# FPGA_SYSTERM.net
KiCad netlist of a schematic drawn in Altium Designer
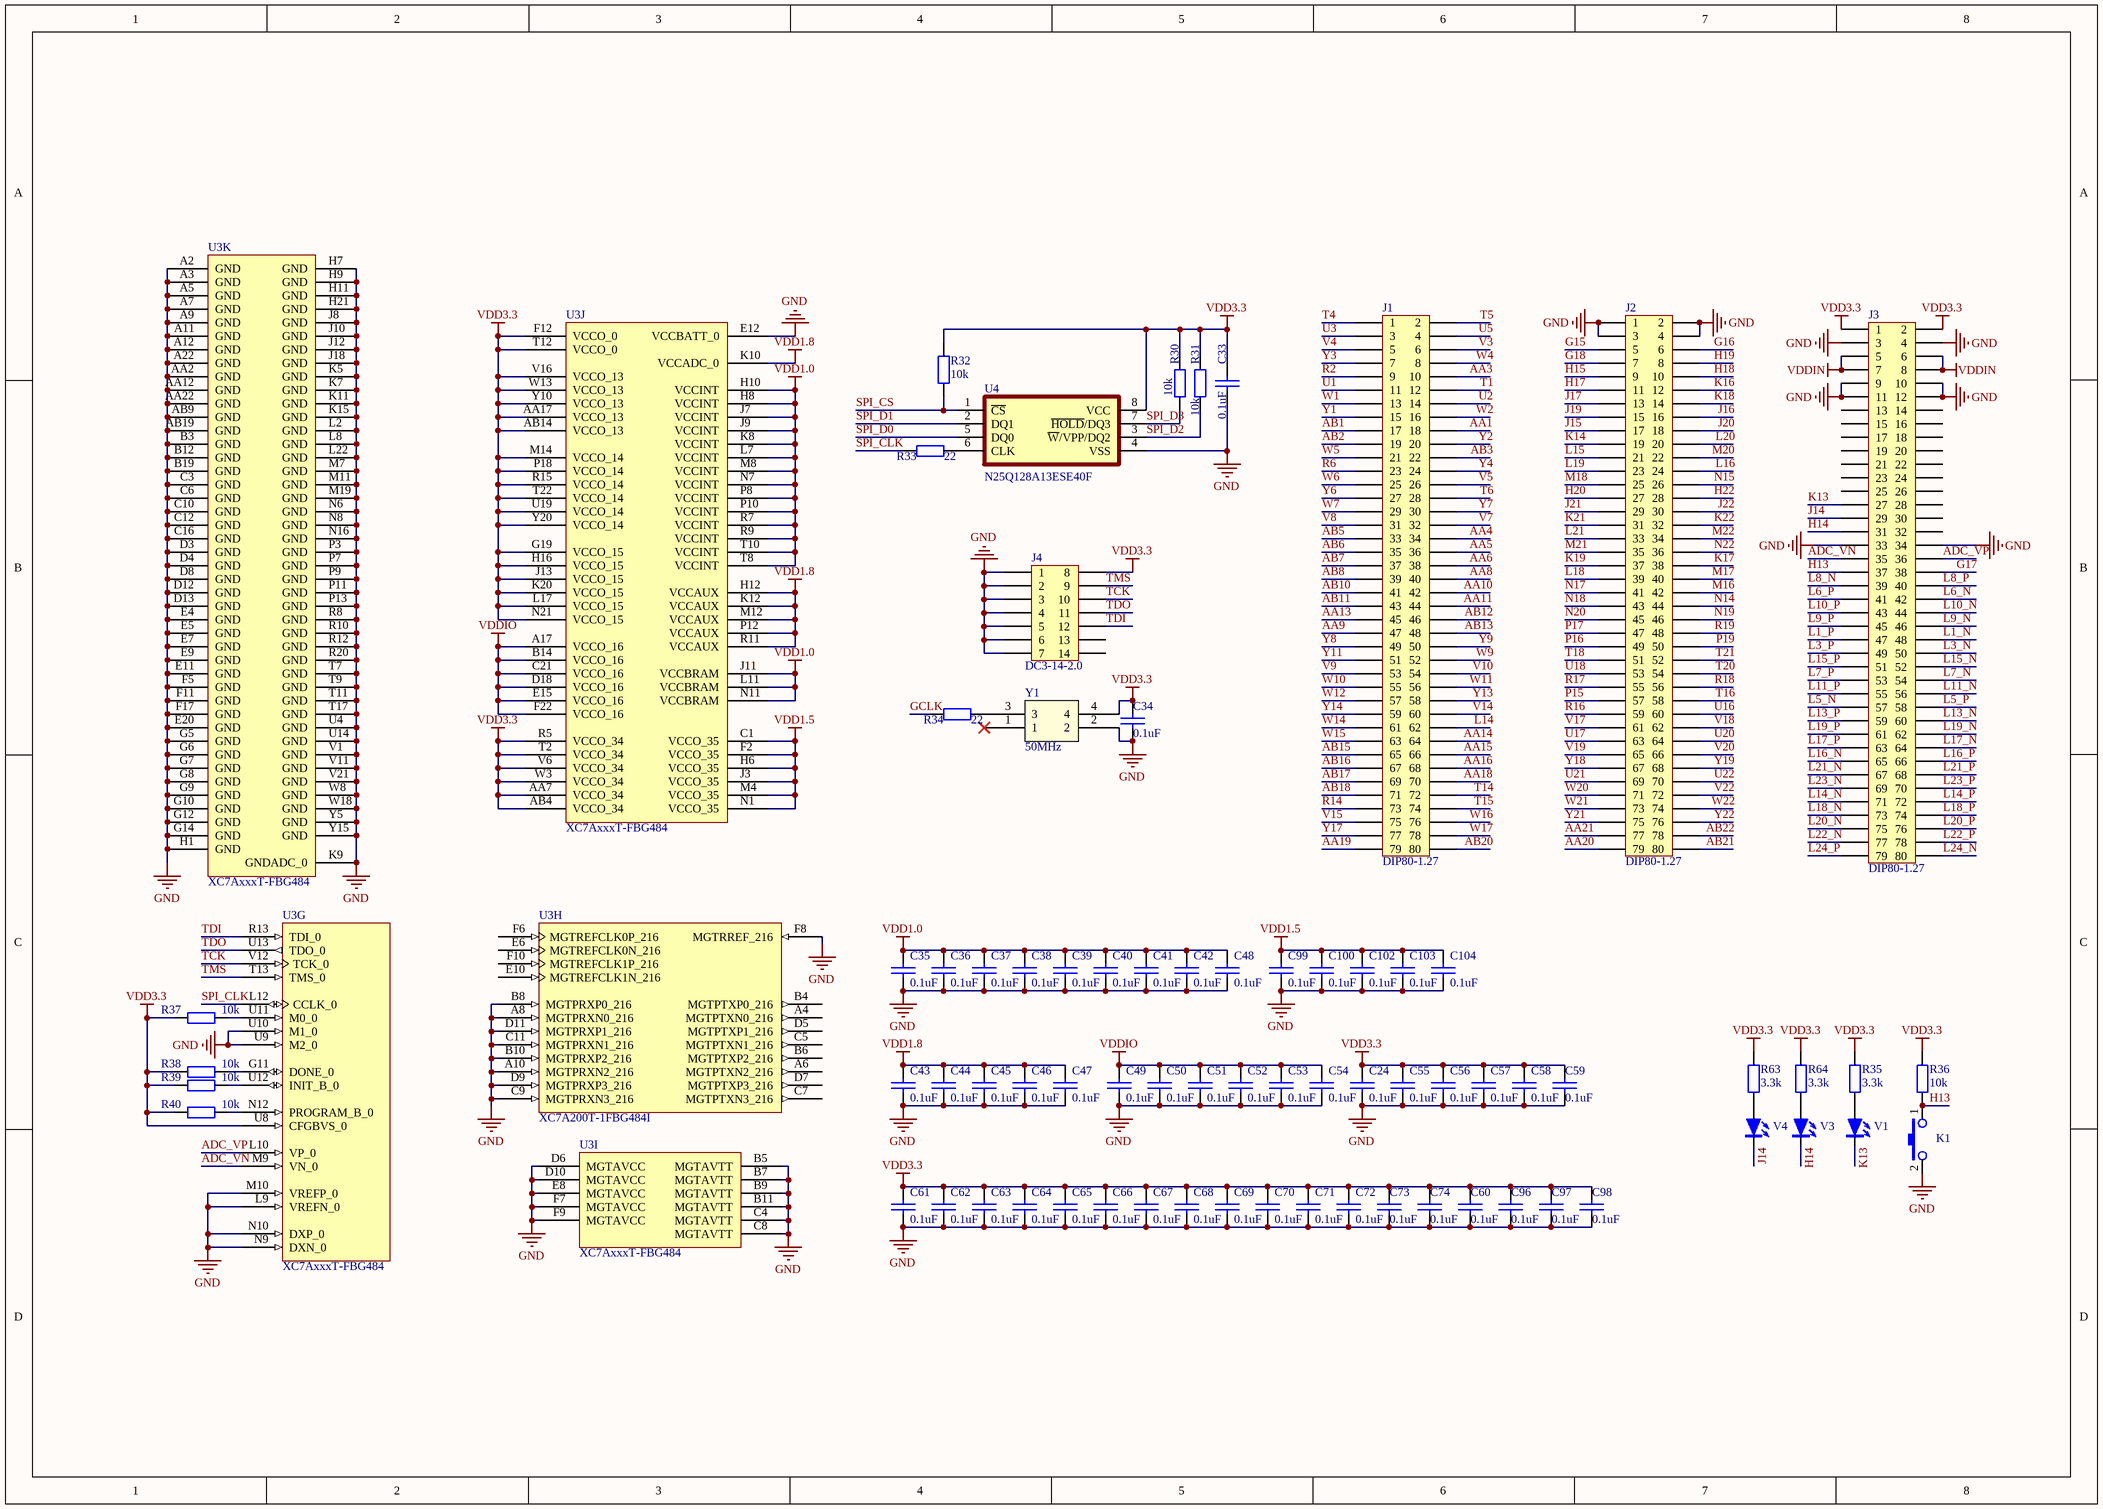
[diagram p0: FPGA SYSTERM.SchDoc]

(export (version "E")
  (design (tool "Eeschema 10.0.6"))
  (components
    (comp (ref "C24") (value "0.1uF") (footprint "0402_c_m") (libsource (lib "My library") (part "CAP")))
    (comp (ref "C33") (value "0.1uF") (footprint "0402_C_M") (libsource (lib "Component") (part "CAP")))
    (comp (ref "C34") (value "0.1uF") (footprint "0402_C_M") (libsource (lib "Component") (part "CAP")))
    (comp (ref "C35") (value "0.1uF") (footprint "0402_C_M") (libsource (lib "Component") (part "CAP")))
    (comp (ref "C36") (value "0.1uF") (footprint "0402_C_M") (libsource (lib "Component") (part "CAP")))
    (comp (ref "C37") (value "0.1uF") (footprint "0402_C_M") (libsource (lib "Component") (part "CAP")))
    (comp (ref "C38") (value "0.1uF") (footprint "0402_C_M") (libsource (lib "Component") (part "CAP")))
    (comp (ref "C39") (value "0.1uF") (footprint "0402_C_M") (libsource (lib "Component") (part "CAP")))
    (comp (ref "C40") (value "0.1uF") (footprint "0402_C_M") (libsource (lib "Component") (part "CAP")))
    (comp (ref "C41") (value "0.1uF") (footprint "0402_C_M") (libsource (lib "Component") (part "CAP")))
    (comp (ref "C42") (value "0.1uF") (footprint "0402_C_M") (libsource (lib "Component") (part "CAP")))
    (comp (ref "C43") (value "0.1uF") (footprint "0402_C_M") (libsource (lib "Component") (part "CAP")))
    (comp (ref "C44") (value "0.1uF") (footprint "0402_C_M") (libsource (lib "Component") (part "CAP")))
    (comp (ref "C45") (value "0.1uF") (footprint "0402_C_M") (libsource (lib "Component") (part "CAP")))
    (comp (ref "C46") (value "0.1uF") (footprint "0402_C_M") (libsource (lib "Component") (part "CAP")))
    (comp (ref "C47") (value "0.1uF") (footprint "0402_C_M") (libsource (lib "Component") (part "CAP")))
    (comp (ref "C48") (value "0.1uF") (footprint "0402_C_M") (libsource (lib "Component") (part "CAP")))
    (comp (ref "C49") (value "0.1uF") (footprint "0402_C_M") (libsource (lib "Component") (part "CAP")))
    (comp (ref "C50") (value "0.1uF") (footprint "0402_C_M") (libsource (lib "Component") (part "CAP")))
    (comp (ref "C51") (value "0.1uF") (footprint "0402_C_M") (libsource (lib "Component") (part "CAP")))
    (comp (ref "C52") (value "0.1uF") (footprint "0402_C_M") (libsource (lib "Component") (part "CAP")))
    (comp (ref "C53") (value "0.1uF") (footprint "0402_C_M") (libsource (lib "Component") (part "CAP")))
    (comp (ref "C54") (value "0.1uF") (footprint "0402_C_M") (libsource (lib "Component") (part "CAP")))
    (comp (ref "C55") (value "0.1uF") (footprint "0402_C_M") (libsource (lib "Component") (part "CAP")))
    (comp (ref "C56") (value "0.1uF") (footprint "0402_C_M") (libsource (lib "Component") (part "CAP")))
    (comp (ref "C57") (value "0.1uF") (footprint "0402_C_M") (libsource (lib "Component") (part "CAP")))
    (comp (ref "C58") (value "0.1uF") (footprint "0402_C_M") (libsource (lib "Component") (part "CAP")))
    (comp (ref "C59") (value "0.1uF") (footprint "0402_C_M") (libsource (lib "Component") (part "CAP")))
    (comp (ref "C60") (value "0.1uF") (footprint "0402_C_M") (libsource (lib "Component") (part "CAP")))
    (comp (ref "C61") (value "0.1uF") (footprint "0402_C_M") (libsource (lib "Component") (part "CAP")))
    (comp (ref "C62") (value "0.1uF") (footprint "0402_C_M") (libsource (lib "Component") (part "CAP")))
    (comp (ref "C63") (value "0.1uF") (footprint "0402_C_M") (libsource (lib "Component") (part "CAP")))
    (comp (ref "C64") (value "0.1uF") (footprint "0402_C_M") (libsource (lib "Component") (part "CAP")))
    (comp (ref "C65") (value "0.1uF") (footprint "0402_C_M") (libsource (lib "Component") (part "CAP")))
    (comp (ref "C66") (value "0.1uF") (footprint "0402_C_M") (libsource (lib "Component") (part "CAP")))
    (comp (ref "C67") (value "0.1uF") (footprint "0402_C_M") (libsource (lib "Component") (part "CAP")))
    (comp (ref "C68") (value "0.1uF") (footprint "0402_C_M") (libsource (lib "Component") (part "CAP")))
    (comp (ref "C69") (value "0.1uF") (footprint "0402_C_M") (libsource (lib "Component") (part "CAP")))
    (comp (ref "C70") (value "0.1uF") (footprint "0402_C_M") (libsource (lib "Component") (part "CAP")))
    (comp (ref "C71") (value "0.1uF") (footprint "0402_C_M") (libsource (lib "Component") (part "CAP")))
    (comp (ref "C72") (value "0.1uF") (footprint "0402_C_M") (libsource (lib "Component") (part "CAP")))
    (comp (ref "C73") (value "0.1uF") (footprint "0402_C_M") (libsource (lib "Component") (part "CAP")))
    (comp (ref "C74") (value "0.1uF") (footprint "0402_C_M") (libsource (lib "Component") (part "CAP")))
    (comp (ref "C96") (value "0.1uF") (footprint "0402_C_M") (libsource (lib "Component") (part "CAP")))
    (comp (ref "C97") (value "0.1uF") (footprint "0402_C_M") (libsource (lib "Component") (part "CAP")))
    (comp (ref "C98") (value "0.1uF") (footprint "0402_C_M") (libsource (lib "Component") (part "CAP")))
    (comp (ref "C99") (value "0.1uF") (footprint "0402_C_M") (libsource (lib "Component") (part "CAP")))
    (comp (ref "C100") (value "0.1uF") (footprint "0402_C_M") (libsource (lib "Component") (part "CAP")))
    (comp (ref "C102") (value "0.1uF") (footprint "0402_C_M") (libsource (lib "Component") (part "CAP")))
    (comp (ref "C103") (value "0.1uF") (footprint "0402_C_M") (libsource (lib "Component") (part "CAP")))
    (comp (ref "C104") (value "0.1uF") (footprint "0402_C_M") (libsource (lib "Component") (part "CAP")))
    (comp (ref "J1")
      (value "DIP80-1.27")
      (footprint "DIP1.27-80")
      (libsource (lib "DIP_SIP") (part "CON80_1"))
    )
    (comp (ref "J2")
      (value "DIP80-1.27")
      (footprint "DIP1.27-80")
      (libsource (lib "DIP_SIP") (part "CON80_1"))
    )
    (comp (ref "J3")
      (value "DIP80-1.27")
      (footprint "DIP1.27-80")
      (libsource (lib "DIP_SIP") (part "CON80_1"))
    )
    (comp (ref "J4") (value "DC3-14-2.0") (footprint "DC3-14-2.0") (libsource (lib "DIP_SIP") (part "CON14")))
    (comp (ref "K1") (value "KEY") (footprint "KEY2") (libsource (lib "Common") (part "KEY1")))
    (comp (ref "R30") (value "10k") (footprint "0402_R_M") (libsource (lib "Common") (part "RES2")))
    (comp (ref "R31") (value "10k") (footprint "0402_R_M") (libsource (lib "Common") (part "RES2")))
    (comp (ref "R32") (value "10k") (footprint "0402_R_M") (libsource (lib "often") (part "RES2")))
    (comp (ref "R33") (value "22") (footprint "0402_R_M") (libsource (lib "Common") (part "RES2")))
    (comp (ref "R34") (value "22") (footprint "0402_R_M") (libsource (lib "Common") (part "RES2")))
    (comp (ref "R35") (value "3.3k") (footprint "0402_R_M") (libsource (lib "Common") (part "RES2")))
    (comp (ref "R36") (value "10k") (footprint "0402_R_M") (libsource (lib "Common") (part "RES2")))
    (comp (ref "R37") (value "10k") (footprint "0402_R_M") (libsource (lib "Common") (part "RES2")))
    (comp (ref "R38") (value "10k") (footprint "0402_R_M") (libsource (lib "Common") (part "RES2")))
    (comp (ref "R39") (value "10k") (footprint "0402_R_M") (libsource (lib "Common") (part "RES2")))
    (comp (ref "R40") (value "10k") (footprint "0402_R_M") (libsource (lib "Common") (part "RES2")))
    (comp (ref "R63") (value "3.3k") (footprint "0402_R_M") (libsource (lib "Common") (part "RES2")))
    (comp (ref "R64") (value "3.3k") (footprint "0402_R_M") (libsource (lib "Common") (part "RES2")))
    (comp (ref "U3")
      (value "XC7AxxxT-FBG484")
      (footprint "FBG484")
      (description "Artix-7 FPGA, 285 User I/Os, 4 GTP, 484-Ball BGA, Speed Grade 1, Industrial Grade, Pb-Free")
      (fields (field (name "GENERIC PART NUMBER") "XC7A200T") (field (name "MANUFACTURER") "Xilinx"))
      (libsource (lib "My Library") (part "XC7A200T-1FBG484I"))
    )
    (comp (ref "U4")
      (value "N25Q128A13ESE40F")
      (footprint "SOP8W")
      (libsource (lib "IC") (part "N25Q128A11EF840E"))
    )
    (comp (ref "V1") (value "LED") (footprint "0805D") (libsource (lib "发光管、数码管") (part "LED2")))
    (comp (ref "V3") (value "LED") (footprint "0805D") (libsource (lib "发光管、数码管") (part "LED2")))
    (comp (ref "V4") (value "LED") (footprint "0805D") (libsource (lib "发光管、数码管") (part "LED2")))
    (comp (ref "Y1")
      (value "50MHz")
      (footprint "OSC 7050-4P")
      (libsource (lib "micro.logic-v1.0") (part "XTAL"))
    )
  )
  (nets
    (net (code "1") (name "/AA1") (class "Default")
      (node (ref "J1") (pin "18") (pinfunction "18_18") (pintype "passive"))
    )
    (net (code "2") (name "/AA3") (class "Default")
      (node (ref "J1") (pin "10") (pinfunction "10_10") (pintype "passive"))
    )
    (net (code "3") (name "/AA4") (class "Default")
      (node (ref "J1") (pin "34") (pinfunction "34_34") (pintype "passive"))
    )
    (net (code "4") (name "/AA5") (class "Default")
      (node (ref "J1") (pin "36") (pinfunction "36_36") (pintype "passive"))
    )
    (net (code "5") (name "/AA6") (class "Default")
      (node (ref "J1") (pin "38") (pinfunction "38_38") (pintype "passive"))
    )
    (net (code "6") (name "/AA8") (class "Default")
      (node (ref "J1") (pin "40") (pinfunction "40_40") (pintype "passive"))
    )
    (net (code "7") (name "/AA9") (class "Default")
      (node (ref "J1") (pin "47") (pinfunction "47_47") (pintype "passive"))
    )
    (net (code "8") (name "/AA10") (class "Default")
      (node (ref "J1") (pin "42") (pinfunction "42_42") (pintype "passive"))
    )
    (net (code "9") (name "/AA11") (class "Default")
      (node (ref "J1") (pin "44") (pinfunction "44_44") (pintype "passive"))
    )
    (net (code "10") (name "/AA13") (class "Default")
      (node (ref "J1") (pin "45") (pinfunction "45_45") (pintype "passive"))
    )
    (net (code "11") (name "/AA14") (class "Default")
      (node (ref "J1") (pin "64") (pinfunction "64_64") (pintype "passive"))
    )
    (net (code "12") (name "/AA15") (class "Default")
      (node (ref "J1") (pin "66") (pinfunction "66_66") (pintype "passive"))
    )
    (net (code "13") (name "/AA16") (class "Default")
      (node (ref "J1") (pin "68") (pinfunction "68_68") (pintype "passive"))
    )
    (net (code "14") (name "/AA18") (class "Default")
      (node (ref "J1") (pin "70") (pinfunction "70_70") (pintype "passive"))
    )
    (net (code "15") (name "/AA19") (class "Default")
      (node (ref "J1") (pin "79") (pinfunction "79_79") (pintype "passive"))
    )
    (net (code "16") (name "/AA20") (class "Default")
      (node (ref "J2") (pin "79") (pinfunction "79_79") (pintype "passive"))
    )
    (net (code "17") (name "/AA21") (class "Default")
      (node (ref "J2") (pin "77") (pinfunction "77_77") (pintype "passive"))
    )
    (net (code "18") (name "/AB1") (class "Default")
      (node (ref "J1") (pin "17") (pinfunction "17_17") (pintype "passive"))
    )
    (net (code "19") (name "/AB2") (class "Default")
      (node (ref "J1") (pin "19") (pinfunction "19_19") (pintype "passive"))
    )
    (net (code "20") (name "/AB3") (class "Default")
      (node (ref "J1") (pin "22") (pinfunction "22_22") (pintype "passive"))
    )
    (net (code "21") (name "/AB5") (class "Default")
      (node (ref "J1") (pin "33") (pinfunction "33_33") (pintype "passive"))
    )
    (net (code "22") (name "/AB6") (class "Default")
      (node (ref "J1") (pin "35") (pinfunction "35_35") (pintype "passive"))
    )
    (net (code "23") (name "/AB7") (class "Default")
      (node (ref "J1") (pin "37") (pinfunction "37_37") (pintype "passive"))
    )
    (net (code "24") (name "/AB8") (class "Default")
      (node (ref "J1") (pin "39") (pinfunction "39_39") (pintype "passive"))
    )
    (net (code "25") (name "/AB10") (class "Default")
      (node (ref "J1") (pin "41") (pinfunction "41_41") (pintype "passive"))
    )
    (net (code "26") (name "/AB11") (class "Default")
      (node (ref "J1") (pin "43") (pinfunction "43_43") (pintype "passive"))
    )
    (net (code "27") (name "/AB12") (class "Default")
      (node (ref "J1") (pin "46") (pinfunction "46_46") (pintype "passive"))
    )
    (net (code "28") (name "/AB13") (class "Default")
      (node (ref "J1") (pin "48") (pinfunction "48_48") (pintype "passive"))
    )
    (net (code "29") (name "/AB15") (class "Default")
      (node (ref "J1") (pin "65") (pinfunction "65_65") (pintype "passive"))
    )
    (net (code "30") (name "/AB16") (class "Default")
      (node (ref "J1") (pin "67") (pinfunction "67_67") (pintype "passive"))
    )
    (net (code "31") (name "/AB17") (class "Default")
      (node (ref "J1") (pin "69") (pinfunction "69_69") (pintype "passive"))
    )
    (net (code "32") (name "/AB18") (class "Default")
      (node (ref "J1") (pin "71") (pinfunction "71_71") (pintype "passive"))
    )
    (net (code "33") (name "/AB20") (class "Default")
      (node (ref "J1") (pin "80") (pinfunction "80_80") (pintype "passive"))
    )
    (net (code "34") (name "/AB21") (class "Default")
      (node (ref "J2") (pin "80") (pinfunction "80_80") (pintype "passive"))
    )
    (net (code "35") (name "/AB22") (class "Default")
      (node (ref "J2") (pin "78") (pinfunction "78_78") (pintype "passive"))
    )
    (net (code "36") (name "/ADC_VN") (class "Default")
      (node (ref "J3") (pin "35") (pinfunction "35_35") (pintype "passive"))
      (node (ref "U3") (pin "M9") (pinfunction "VN_0_M9") (pintype "input"))
    )
    (net (code "37") (name "/ADC_VP") (class "Default")
      (node (ref "J3") (pin "36") (pinfunction "36_36") (pintype "passive"))
      (node (ref "U3") (pin "L10") (pinfunction "VP_0_L10") (pintype "input"))
    )
    (net (code "38") (name "/G15") (class "Default")
      (node (ref "J2") (pin "5") (pinfunction "5_5") (pintype "passive"))
    )
    (net (code "39") (name "/G16") (class "Default")
      (node (ref "J2") (pin "6") (pinfunction "6_6") (pintype "passive"))
    )
    (net (code "40") (name "/G17") (class "Default")
      (node (ref "J3") (pin "38") (pinfunction "38_38") (pintype "passive"))
    )
    (net (code "41") (name "/G18") (class "Default")
      (node (ref "J2") (pin "7") (pinfunction "7_7") (pintype "passive"))
    )
    (net (code "42") (name "/GCLK") (class "Default") (node (ref "R34") (pin "2") (pintype "passive")))
    (net (code "43") (name "/H13") (class "Default")
      (node (ref "J3") (pin "37") (pinfunction "37_37") (pintype "passive"))
      (node (ref "K1") (pin "1") (pintype "passive"))
      (node (ref "R36") (pin "1") (pintype "passive"))
    )
    (net (code "44") (name "/H14") (class "Default")
      (node (ref "J3") (pin "31") (pinfunction "31_31") (pintype "passive"))
      (node (ref "V3") (pin "2") (pinfunction "2_2") (pintype "passive"))
    )
    (net (code "45") (name "/H15") (class "Default")
      (node (ref "J2") (pin "9") (pinfunction "9_9") (pintype "passive"))
    )
    (net (code "46") (name "/H17") (class "Default")
      (node (ref "J2") (pin "11") (pinfunction "11_11") (pintype "passive"))
    )
    (net (code "47") (name "/H18") (class "Default")
      (node (ref "J2") (pin "10") (pinfunction "10_10") (pintype "passive"))
    )
    (net (code "48") (name "/H19") (class "Default")
      (node (ref "J2") (pin "8") (pinfunction "8_8") (pintype "passive"))
    )
    (net (code "49") (name "/H20") (class "Default")
      (node (ref "J2") (pin "27") (pinfunction "27_27") (pintype "passive"))
    )
    (net (code "50") (name "/H22") (class "Default")
      (node (ref "J2") (pin "28") (pinfunction "28_28") (pintype "passive"))
    )
    (net (code "51") (name "/J14") (class "Default")
      (node (ref "J3") (pin "29") (pinfunction "29_29") (pintype "passive"))
      (node (ref "V4") (pin "2") (pinfunction "2_2") (pintype "passive"))
    )
    (net (code "52") (name "/J15") (class "Default")
      (node (ref "J2") (pin "17") (pinfunction "17_17") (pintype "passive"))
    )
    (net (code "53") (name "/J16") (class "Default")
      (node (ref "J2") (pin "16") (pinfunction "16_16") (pintype "passive"))
    )
    (net (code "54") (name "/J17") (class "Default")
      (node (ref "J2") (pin "13") (pinfunction "13_13") (pintype "passive"))
    )
    (net (code "55") (name "/J19") (class "Default")
      (node (ref "J2") (pin "15") (pinfunction "15_15") (pintype "passive"))
    )
    (net (code "56") (name "/J20") (class "Default")
      (node (ref "J2") (pin "18") (pinfunction "18_18") (pintype "passive"))
    )
    (net (code "57") (name "/J21") (class "Default")
      (node (ref "J2") (pin "29") (pinfunction "29_29") (pintype "passive"))
    )
    (net (code "58") (name "/J22") (class "Default")
      (node (ref "J2") (pin "30") (pinfunction "30_30") (pintype "passive"))
    )
    (net (code "59") (name "/K13") (class "Default")
      (node (ref "J3") (pin "27") (pinfunction "27_27") (pintype "passive"))
      (node (ref "V1") (pin "2") (pinfunction "2_2") (pintype "passive"))
    )
    (net (code "60") (name "/K14") (class "Default")
      (node (ref "J2") (pin "19") (pinfunction "19_19") (pintype "passive"))
    )
    (net (code "61") (name "/K16") (class "Default")
      (node (ref "J2") (pin "12") (pinfunction "12_12") (pintype "passive"))
    )
    (net (code "62") (name "/K17") (class "Default")
      (node (ref "J2") (pin "38") (pinfunction "38_38") (pintype "passive"))
    )
    (net (code "63") (name "/K18") (class "Default")
      (node (ref "J2") (pin "14") (pinfunction "14_14") (pintype "passive"))
    )
    (net (code "64") (name "/K19") (class "Default")
      (node (ref "J2") (pin "37") (pinfunction "37_37") (pintype "passive"))
    )
    (net (code "65") (name "/K21") (class "Default")
      (node (ref "J2") (pin "31") (pinfunction "31_31") (pintype "passive"))
    )
    (net (code "66") (name "/K22") (class "Default")
      (node (ref "J2") (pin "32") (pinfunction "32_32") (pintype "passive"))
    )
    (net (code "67") (name "/L1_N") (class "Default")
      (node (ref "J3") (pin "48") (pinfunction "48_48") (pintype "passive"))
    )
    (net (code "68") (name "/L1_P") (class "Default")
      (node (ref "J3") (pin "47") (pinfunction "47_47") (pintype "passive"))
    )
    (net (code "69") (name "/L3_N") (class "Default")
      (node (ref "J3") (pin "50") (pinfunction "50_50") (pintype "passive"))
    )
    (net (code "70") (name "/L3_P") (class "Default")
      (node (ref "J3") (pin "49") (pinfunction "49_49") (pintype "passive"))
    )
    (net (code "71") (name "/L5_N") (class "Default")
      (node (ref "J3") (pin "57") (pinfunction "57_57") (pintype "passive"))
    )
    (net (code "72") (name "/L5_P") (class "Default")
      (node (ref "J3") (pin "58") (pinfunction "58_58") (pintype "passive"))
    )
    (net (code "73") (name "/L6_N") (class "Default")
      (node (ref "J3") (pin "42") (pinfunction "42_42") (pintype "passive"))
    )
    (net (code "74") (name "/L6_P") (class "Default")
      (node (ref "J3") (pin "41") (pinfunction "41_41") (pintype "passive"))
    )
    (net (code "75") (name "/L7_N") (class "Default")
      (node (ref "J3") (pin "54") (pinfunction "54_54") (pintype "passive"))
    )
    (net (code "76") (name "/L7_P") (class "Default")
      (node (ref "J3") (pin "53") (pinfunction "53_53") (pintype "passive"))
    )
    (net (code "77") (name "/L8_N") (class "Default")
      (node (ref "J3") (pin "39") (pinfunction "39_39") (pintype "passive"))
    )
    (net (code "78") (name "/L8_P") (class "Default")
      (node (ref "J3") (pin "40") (pinfunction "40_40") (pintype "passive"))
    )
    (net (code "79") (name "/L9_N") (class "Default")
      (node (ref "J3") (pin "46") (pinfunction "46_46") (pintype "passive"))
    )
    (net (code "80") (name "/L9_P") (class "Default")
      (node (ref "J3") (pin "45") (pinfunction "45_45") (pintype "passive"))
    )
    (net (code "81") (name "/L10_N") (class "Default")
      (node (ref "J3") (pin "44") (pinfunction "44_44") (pintype "passive"))
    )
    (net (code "82") (name "/L10_P") (class "Default")
      (node (ref "J3") (pin "43") (pinfunction "43_43") (pintype "passive"))
    )
    (net (code "83") (name "/L11_N") (class "Default")
      (node (ref "J3") (pin "56") (pinfunction "56_56") (pintype "passive"))
    )
    (net (code "84") (name "/L11_P") (class "Default")
      (node (ref "J3") (pin "55") (pinfunction "55_55") (pintype "passive"))
    )
    (net (code "85") (name "/L13_N") (class "Default")
      (node (ref "J3") (pin "60") (pinfunction "60_60") (pintype "passive"))
    )
    (net (code "86") (name "/L13_P") (class "Default")
      (node (ref "J3") (pin "59") (pinfunction "59_59") (pintype "passive"))
    )
    (net (code "87") (name "/L14") (class "Default")
      (node (ref "J1") (pin "62") (pinfunction "62_62") (pintype "passive"))
    )
    (net (code "88") (name "/L14_N") (class "Default")
      (node (ref "J3") (pin "71") (pinfunction "71_71") (pintype "passive"))
    )
    (net (code "89") (name "/L14_P") (class "Default")
      (node (ref "J3") (pin "72") (pinfunction "72_72") (pintype "passive"))
    )
    (net (code "90") (name "/L15") (class "Default")
      (node (ref "J2") (pin "21") (pinfunction "21_21") (pintype "passive"))
    )
    (net (code "91") (name "/L15_N") (class "Default")
      (node (ref "J3") (pin "52") (pinfunction "52_52") (pintype "passive"))
    )
    (net (code "92") (name "/L15_P") (class "Default")
      (node (ref "J3") (pin "51") (pinfunction "51_51") (pintype "passive"))
    )
    (net (code "93") (name "/L16") (class "Default")
      (node (ref "J2") (pin "24") (pinfunction "24_24") (pintype "passive"))
    )
    (net (code "94") (name "/L16_N") (class "Default")
      (node (ref "J3") (pin "65") (pinfunction "65_65") (pintype "passive"))
    )
    (net (code "95") (name "/L16_P") (class "Default")
      (node (ref "J3") (pin "66") (pinfunction "66_66") (pintype "passive"))
    )
    (net (code "96") (name "/L17_N") (class "Default")
      (node (ref "J3") (pin "64") (pinfunction "64_64") (pintype "passive"))
    )
    (net (code "97") (name "/L17_P") (class "Default")
      (node (ref "J3") (pin "63") (pinfunction "63_63") (pintype "passive"))
    )
    (net (code "98") (name "/L18") (class "Default")
      (node (ref "J2") (pin "39") (pinfunction "39_39") (pintype "passive"))
    )
    (net (code "99") (name "/L18_N") (class "Default")
      (node (ref "J3") (pin "73") (pinfunction "73_73") (pintype "passive"))
    )
    (net (code "100") (name "/L18_P") (class "Default")
      (node (ref "J3") (pin "74") (pinfunction "74_74") (pintype "passive"))
    )
    (net (code "101") (name "/L19") (class "Default")
      (node (ref "J2") (pin "23") (pinfunction "23_23") (pintype "passive"))
    )
    (net (code "102") (name "/L19_N") (class "Default")
      (node (ref "J3") (pin "62") (pinfunction "62_62") (pintype "passive"))
    )
    (net (code "103") (name "/L19_P") (class "Default")
      (node (ref "J3") (pin "61") (pinfunction "61_61") (pintype "passive"))
    )
    (net (code "104") (name "/L20") (class "Default")
      (node (ref "J2") (pin "20") (pinfunction "20_20") (pintype "passive"))
    )
    (net (code "105") (name "/L20_N") (class "Default")
      (node (ref "J3") (pin "75") (pinfunction "75_75") (pintype "passive"))
    )
    (net (code "106") (name "/L20_P") (class "Default")
      (node (ref "J3") (pin "76") (pinfunction "76_76") (pintype "passive"))
    )
    (net (code "107") (name "/L21") (class "Default")
      (node (ref "J2") (pin "33") (pinfunction "33_33") (pintype "passive"))
    )
    (net (code "108") (name "/L21_N") (class "Default")
      (node (ref "J3") (pin "67") (pinfunction "67_67") (pintype "passive"))
    )
    (net (code "109") (name "/L21_P") (class "Default")
      (node (ref "J3") (pin "68") (pinfunction "68_68") (pintype "passive"))
    )
    (net (code "110") (name "/L22_N") (class "Default")
      (node (ref "J3") (pin "77") (pinfunction "77_77") (pintype "passive"))
    )
    (net (code "111") (name "/L22_P") (class "Default")
      (node (ref "J3") (pin "78") (pinfunction "78_78") (pintype "passive"))
    )
    (net (code "112") (name "/L23_N") (class "Default")
      (node (ref "J3") (pin "69") (pinfunction "69_69") (pintype "passive"))
    )
    (net (code "113") (name "/L23_P") (class "Default")
      (node (ref "J3") (pin "70") (pinfunction "70_70") (pintype "passive"))
    )
    (net (code "114") (name "/L24_N") (class "Default")
      (node (ref "J3") (pin "80") (pinfunction "80_80") (pintype "passive"))
    )
    (net (code "115") (name "/L24_P") (class "Default")
      (node (ref "J3") (pin "79") (pinfunction "79_79") (pintype "passive"))
    )
    (net (code "116") (name "/M16") (class "Default")
      (node (ref "J2") (pin "42") (pinfunction "42_42") (pintype "passive"))
    )
    (net (code "117") (name "/M17") (class "Default")
      (node (ref "J2") (pin "40") (pinfunction "40_40") (pintype "passive"))
    )
    (net (code "118") (name "/M18") (class "Default")
      (node (ref "J2") (pin "25") (pinfunction "25_25") (pintype "passive"))
    )
    (net (code "119") (name "/M20") (class "Default")
      (node (ref "J2") (pin "22") (pinfunction "22_22") (pintype "passive"))
    )
    (net (code "120") (name "/M21") (class "Default")
      (node (ref "J2") (pin "35") (pinfunction "35_35") (pintype "passive"))
    )
    (net (code "121") (name "/M22") (class "Default")
      (node (ref "J2") (pin "34") (pinfunction "34_34") (pintype "passive"))
    )
    (net (code "122") (name "/N14") (class "Default")
      (node (ref "J2") (pin "44") (pinfunction "44_44") (pintype "passive"))
    )
    (net (code "123") (name "/N15") (class "Default")
      (node (ref "J2") (pin "26") (pinfunction "26_26") (pintype "passive"))
    )
    (net (code "124") (name "/N17") (class "Default")
      (node (ref "J2") (pin "41") (pinfunction "41_41") (pintype "passive"))
    )
    (net (code "125") (name "/N18") (class "Default")
      (node (ref "J2") (pin "43") (pinfunction "43_43") (pintype "passive"))
    )
    (net (code "126") (name "/N19") (class "Default")
      (node (ref "J2") (pin "46") (pinfunction "46_46") (pintype "passive"))
    )
    (net (code "127") (name "/N20") (class "Default")
      (node (ref "J2") (pin "45") (pinfunction "45_45") (pintype "passive"))
    )
    (net (code "128") (name "/N22") (class "Default")
      (node (ref "J2") (pin "36") (pinfunction "36_36") (pintype "passive"))
    )
    (net (code "129") (name "/P15") (class "Default")
      (node (ref "J2") (pin "57") (pinfunction "57_57") (pintype "passive"))
    )
    (net (code "130") (name "/P16") (class "Default")
      (node (ref "J2") (pin "49") (pinfunction "49_49") (pintype "passive"))
    )
    (net (code "131") (name "/P17") (class "Default")
      (node (ref "J2") (pin "47") (pinfunction "47_47") (pintype "passive"))
    )
    (net (code "132") (name "/P19") (class "Default")
      (node (ref "J2") (pin "50") (pinfunction "50_50") (pintype "passive"))
    )
    (net (code "133") (name "/R2") (class "Default")
      (node (ref "J1") (pin "9") (pinfunction "9_9") (pintype "passive"))
    )
    (net (code "134") (name "/R6") (class "Default")
      (node (ref "J1") (pin "23") (pinfunction "23_23") (pintype "passive"))
    )
    (net (code "135") (name "/R14") (class "Default")
      (node (ref "J1") (pin "73") (pinfunction "73_73") (pintype "passive"))
    )
    (net (code "136") (name "/R16") (class "Default")
      (node (ref "J2") (pin "59") (pinfunction "59_59") (pintype "passive"))
    )
    (net (code "137") (name "/R17") (class "Default")
      (node (ref "J2") (pin "55") (pinfunction "55_55") (pintype "passive"))
    )
    (net (code "138") (name "/R18") (class "Default")
      (node (ref "J2") (pin "56") (pinfunction "56_56") (pintype "passive"))
    )
    (net (code "139") (name "/R19") (class "Default")
      (node (ref "J2") (pin "48") (pinfunction "48_48") (pintype "passive"))
    )
    (net (code "140") (name "/SPI_CLK") (class "Default")
      (node (ref "R33") (pin "2") (pintype "passive"))
      (node (ref "U3") (pin "L12") (pinfunction "CCLK_0_L12") (pintype "bidirectional"))
    )
    (net (code "141") (name "/SPI_CS") (class "Default")
      (node (ref "R32") (pin "2") (pintype "passive"))
      (node (ref "U4") (pin "1") (pinfunction "~{CS}_1") (pintype "passive"))
    )
    (net (code "142") (name "/SPI_D0") (class "Default")
      (node (ref "U4") (pin "5") (pinfunction "DQ0_5") (pintype "passive"))
    )
    (net (code "143") (name "/SPI_D1") (class "Default")
      (node (ref "U4") (pin "2") (pinfunction "DQ1_2") (pintype "passive"))
    )
    (net (code "144") (name "/SPI_D2") (class "Default")
      (node (ref "R31") (pin "1") (pintype "passive"))
      (node (ref "U4") (pin "3") (pinfunction "~{W}/VPP/DQ2_3") (pintype "passive"))
    )
    (net (code "145") (name "/SPI_D3") (class "Default")
      (node (ref "R30") (pin "1") (pintype "passive"))
      (node (ref "U4") (pin "7") (pinfunction "~{HOLD}/DQ3_7") (pintype "passive"))
    )
    (net (code "146") (name "/T1") (class "Default")
      (node (ref "J1") (pin "12") (pinfunction "12_12") (pintype "passive"))
    )
    (net (code "147") (name "/T4") (class "Default")
      (node (ref "J1") (pin "1") (pinfunction "1_1") (pintype "passive"))
    )
    (net (code "148") (name "/T5") (class "Default")
      (node (ref "J1") (pin "2") (pinfunction "2_2") (pintype "passive"))
    )
    (net (code "149") (name "/T6") (class "Default")
      (node (ref "J1") (pin "28") (pinfunction "28_28") (pintype "passive"))
    )
    (net (code "150") (name "/T14") (class "Default")
      (node (ref "J1") (pin "72") (pinfunction "72_72") (pintype "passive"))
    )
    (net (code "151") (name "/T15") (class "Default")
      (node (ref "J1") (pin "74") (pinfunction "74_74") (pintype "passive"))
    )
    (net (code "152") (name "/T16") (class "Default")
      (node (ref "J2") (pin "58") (pinfunction "58_58") (pintype "passive"))
    )
    (net (code "153") (name "/T18") (class "Default")
      (node (ref "J2") (pin "51") (pinfunction "51_51") (pintype "passive"))
    )
    (net (code "154") (name "/T20") (class "Default")
      (node (ref "J2") (pin "54") (pinfunction "54_54") (pintype "passive"))
    )
    (net (code "155") (name "/T21") (class "Default")
      (node (ref "J2") (pin "52") (pinfunction "52_52") (pintype "passive"))
    )
    (net (code "156") (name "/TCK") (class "Default")
      (node (ref "J4") (pin "10") (pinfunction "10_10") (pintype "passive"))
      (node (ref "U3") (pin "V12") (pinfunction "TCK_0_V12") (pintype "input"))
    )
    (net (code "157") (name "/TDI") (class "Default")
      (node (ref "J4") (pin "12") (pinfunction "12_12") (pintype "passive"))
      (node (ref "U3") (pin "R13") (pinfunction "TDI_0_R13") (pintype "input"))
    )
    (net (code "158") (name "/TDO") (class "Default")
      (node (ref "J4") (pin "11") (pinfunction "11_11") (pintype "passive"))
      (node (ref "U3") (pin "U13") (pinfunction "TDO_0_U13") (pintype "output"))
    )
    (net (code "159") (name "/TMS") (class "Default")
      (node (ref "J4") (pin "9") (pinfunction "9_9") (pintype "passive"))
      (node (ref "U3") (pin "T13") (pinfunction "TMS_0_T13") (pintype "input"))
    )
    (net (code "160") (name "/U1") (class "Default")
      (node (ref "J1") (pin "11") (pinfunction "11_11") (pintype "passive"))
    )
    (net (code "161") (name "/U2") (class "Default")
      (node (ref "J1") (pin "14") (pinfunction "14_14") (pintype "passive"))
    )
    (net (code "162") (name "/U3") (class "Default")
      (node (ref "J1") (pin "3") (pinfunction "3_3") (pintype "passive"))
    )
    (net (code "163") (name "/U5") (class "Default")
      (node (ref "J1") (pin "4") (pinfunction "4_4") (pintype "passive"))
    )
    (net (code "164") (name "/U16") (class "Default")
      (node (ref "J2") (pin "60") (pinfunction "60_60") (pintype "passive"))
    )
    (net (code "165") (name "/U17") (class "Default")
      (node (ref "J2") (pin "63") (pinfunction "63_63") (pintype "passive"))
    )
    (net (code "166") (name "/U18") (class "Default")
      (node (ref "J2") (pin "53") (pinfunction "53_53") (pintype "passive"))
    )
    (net (code "167") (name "/U20") (class "Default")
      (node (ref "J2") (pin "64") (pinfunction "64_64") (pintype "passive"))
    )
    (net (code "168") (name "/U21") (class "Default")
      (node (ref "J2") (pin "69") (pinfunction "69_69") (pintype "passive"))
    )
    (net (code "169") (name "/U22") (class "Default")
      (node (ref "J2") (pin "70") (pinfunction "70_70") (pintype "passive"))
    )
    (net (code "170") (name "/V3") (class "Default")
      (node (ref "J1") (pin "6") (pinfunction "6_6") (pintype "passive"))
    )
    (net (code "171") (name "/V4") (class "Default")
      (node (ref "J1") (pin "5") (pinfunction "5_5") (pintype "passive"))
    )
    (net (code "172") (name "/V5") (class "Default")
      (node (ref "J1") (pin "26") (pinfunction "26_26") (pintype "passive"))
    )
    (net (code "173") (name "/V7") (class "Default")
      (node (ref "J1") (pin "32") (pinfunction "32_32") (pintype "passive"))
    )
    (net (code "174") (name "/V8") (class "Default")
      (node (ref "J1") (pin "31") (pinfunction "31_31") (pintype "passive"))
    )
    (net (code "175") (name "/V9") (class "Default")
      (node (ref "J1") (pin "53") (pinfunction "53_53") (pintype "passive"))
    )
    (net (code "176") (name "/V10") (class "Default")
      (node (ref "J1") (pin "54") (pinfunction "54_54") (pintype "passive"))
    )
    (net (code "177") (name "/V14") (class "Default")
      (node (ref "J1") (pin "60") (pinfunction "60_60") (pintype "passive"))
    )
    (net (code "178") (name "/V15") (class "Default")
      (node (ref "J1") (pin "75") (pinfunction "75_75") (pintype "passive"))
    )
    (net (code "179") (name "/V17") (class "Default")
      (node (ref "J2") (pin "61") (pinfunction "61_61") (pintype "passive"))
    )
    (net (code "180") (name "/V18") (class "Default")
      (node (ref "J2") (pin "62") (pinfunction "62_62") (pintype "passive"))
    )
    (net (code "181") (name "/V19") (class "Default")
      (node (ref "J2") (pin "65") (pinfunction "65_65") (pintype "passive"))
    )
    (net (code "182") (name "/V20") (class "Default")
      (node (ref "J2") (pin "66") (pinfunction "66_66") (pintype "passive"))
    )
    (net (code "183") (name "/V22") (class "Default")
      (node (ref "J2") (pin "72") (pinfunction "72_72") (pintype "passive"))
    )
    (net (code "184") (name "/W1") (class "Default")
      (node (ref "J1") (pin "13") (pinfunction "13_13") (pintype "passive"))
    )
    (net (code "185") (name "/W2") (class "Default")
      (node (ref "J1") (pin "16") (pinfunction "16_16") (pintype "passive"))
    )
    (net (code "186") (name "/W4") (class "Default")
      (node (ref "J1") (pin "8") (pinfunction "8_8") (pintype "passive"))
    )
    (net (code "187") (name "/W5") (class "Default")
      (node (ref "J1") (pin "21") (pinfunction "21_21") (pintype "passive"))
    )
    (net (code "188") (name "/W6") (class "Default")
      (node (ref "J1") (pin "25") (pinfunction "25_25") (pintype "passive"))
    )
    (net (code "189") (name "/W7") (class "Default")
      (node (ref "J1") (pin "29") (pinfunction "29_29") (pintype "passive"))
    )
    (net (code "190") (name "/W9") (class "Default")
      (node (ref "J1") (pin "52") (pinfunction "52_52") (pintype "passive"))
    )
    (net (code "191") (name "/W10") (class "Default")
      (node (ref "J1") (pin "55") (pinfunction "55_55") (pintype "passive"))
    )
    (net (code "192") (name "/W11") (class "Default")
      (node (ref "J1") (pin "56") (pinfunction "56_56") (pintype "passive"))
    )
    (net (code "193") (name "/W12") (class "Default")
      (node (ref "J1") (pin "57") (pinfunction "57_57") (pintype "passive"))
    )
    (net (code "194") (name "/W14") (class "Default")
      (node (ref "J1") (pin "61") (pinfunction "61_61") (pintype "passive"))
    )
    (net (code "195") (name "/W15") (class "Default")
      (node (ref "J1") (pin "63") (pinfunction "63_63") (pintype "passive"))
    )
    (net (code "196") (name "/W16") (class "Default")
      (node (ref "J1") (pin "76") (pinfunction "76_76") (pintype "passive"))
    )
    (net (code "197") (name "/W17") (class "Default")
      (node (ref "J1") (pin "78") (pinfunction "78_78") (pintype "passive"))
    )
    (net (code "198") (name "/W20") (class "Default")
      (node (ref "J2") (pin "71") (pinfunction "71_71") (pintype "passive"))
    )
    (net (code "199") (name "/W21") (class "Default")
      (node (ref "J2") (pin "73") (pinfunction "73_73") (pintype "passive"))
    )
    (net (code "200") (name "/W22") (class "Default")
      (node (ref "J2") (pin "74") (pinfunction "74_74") (pintype "passive"))
    )
    (net (code "201") (name "/Y1") (class "Default")
      (node (ref "J1") (pin "15") (pinfunction "15_15") (pintype "passive"))
    )
    (net (code "202") (name "/Y2") (class "Default")
      (node (ref "J1") (pin "20") (pinfunction "20_20") (pintype "passive"))
    )
    (net (code "203") (name "/Y3") (class "Default")
      (node (ref "J1") (pin "7") (pinfunction "7_7") (pintype "passive"))
    )
    (net (code "204") (name "/Y4") (class "Default")
      (node (ref "J1") (pin "24") (pinfunction "24_24") (pintype "passive"))
    )
    (net (code "205") (name "/Y6") (class "Default")
      (node (ref "J1") (pin "27") (pinfunction "27_27") (pintype "passive"))
    )
    (net (code "206") (name "/Y7") (class "Default")
      (node (ref "J1") (pin "30") (pinfunction "30_30") (pintype "passive"))
    )
    (net (code "207") (name "/Y8") (class "Default")
      (node (ref "J1") (pin "49") (pinfunction "49_49") (pintype "passive"))
    )
    (net (code "208") (name "/Y9") (class "Default")
      (node (ref "J1") (pin "50") (pinfunction "50_50") (pintype "passive"))
    )
    (net (code "209") (name "/Y11") (class "Default")
      (node (ref "J1") (pin "51") (pinfunction "51_51") (pintype "passive"))
    )
    (net (code "210") (name "/Y13") (class "Default")
      (node (ref "J1") (pin "58") (pinfunction "58_58") (pintype "passive"))
    )
    (net (code "211") (name "/Y14") (class "Default")
      (node (ref "J1") (pin "59") (pinfunction "59_59") (pintype "passive"))
    )
    (net (code "212") (name "/Y17") (class "Default")
      (node (ref "J1") (pin "77") (pinfunction "77_77") (pintype "passive"))
    )
    (net (code "213") (name "/Y18") (class "Default")
      (node (ref "J2") (pin "67") (pinfunction "67_67") (pintype "passive"))
    )
    (net (code "214") (name "/Y19") (class "Default")
      (node (ref "J2") (pin "68") (pinfunction "68_68") (pintype "passive"))
    )
    (net (code "215") (name "/Y21") (class "Default")
      (node (ref "J2") (pin "75") (pinfunction "75_75") (pintype "passive"))
    )
    (net (code "216") (name "/Y22") (class "Default")
      (node (ref "J2") (pin "76") (pinfunction "76_76") (pintype "passive"))
    )
    (net (code "217") (name "GND") (class "Default")
      (node (ref "C100") (pin "2") (pinfunction "2_2") (pintype "passive"))
      (node (ref "C102") (pin "2") (pinfunction "2_2") (pintype "passive"))
      (node (ref "C103") (pin "2") (pinfunction "2_2") (pintype "passive"))
      (node (ref "C104") (pin "2") (pinfunction "2_2") (pintype "passive"))
      (node (ref "C24") (pin "2") (pinfunction "2_2") (pintype "passive"))
      (node (ref "C33") (pin "2") (pinfunction "2_2") (pintype "passive"))
      (node (ref "C34") (pin "2") (pinfunction "2_2") (pintype "passive"))
      (node (ref "C35") (pin "2") (pinfunction "2_2") (pintype "passive"))
      (node (ref "C36") (pin "2") (pinfunction "2_2") (pintype "passive"))
      (node (ref "C37") (pin "2") (pinfunction "2_2") (pintype "passive"))
      (node (ref "C38") (pin "2") (pinfunction "2_2") (pintype "passive"))
      (node (ref "C39") (pin "2") (pinfunction "2_2") (pintype "passive"))
      (node (ref "C40") (pin "2") (pinfunction "2_2") (pintype "passive"))
      (node (ref "C41") (pin "2") (pinfunction "2_2") (pintype "passive"))
      (node (ref "C42") (pin "2") (pinfunction "2_2") (pintype "passive"))
      (node (ref "C43") (pin "2") (pinfunction "2_2") (pintype "passive"))
      (node (ref "C44") (pin "2") (pinfunction "2_2") (pintype "passive"))
      (node (ref "C45") (pin "2") (pinfunction "2_2") (pintype "passive"))
      (node (ref "C46") (pin "2") (pinfunction "2_2") (pintype "passive"))
      (node (ref "C47") (pin "2") (pinfunction "2_2") (pintype "passive"))
      (node (ref "C48") (pin "2") (pinfunction "2_2") (pintype "passive"))
      (node (ref "C49") (pin "2") (pinfunction "2_2") (pintype "passive"))
      (node (ref "C50") (pin "2") (pinfunction "2_2") (pintype "passive"))
      (node (ref "C51") (pin "2") (pinfunction "2_2") (pintype "passive"))
      (node (ref "C52") (pin "2") (pinfunction "2_2") (pintype "passive"))
      (node (ref "C53") (pin "2") (pinfunction "2_2") (pintype "passive"))
      (node (ref "C54") (pin "2") (pinfunction "2_2") (pintype "passive"))
      (node (ref "C55") (pin "2") (pinfunction "2_2") (pintype "passive"))
      (node (ref "C56") (pin "2") (pinfunction "2_2") (pintype "passive"))
      (node (ref "C57") (pin "2") (pinfunction "2_2") (pintype "passive"))
      (node (ref "C58") (pin "2") (pinfunction "2_2") (pintype "passive"))
      (node (ref "C59") (pin "2") (pinfunction "2_2") (pintype "passive"))
      (node (ref "C60") (pin "2") (pinfunction "2_2") (pintype "passive"))
      (node (ref "C61") (pin "2") (pinfunction "2_2") (pintype "passive"))
      (node (ref "C62") (pin "2") (pinfunction "2_2") (pintype "passive"))
      (node (ref "C63") (pin "2") (pinfunction "2_2") (pintype "passive"))
      (node (ref "C64") (pin "2") (pinfunction "2_2") (pintype "passive"))
      (node (ref "C65") (pin "2") (pinfunction "2_2") (pintype "passive"))
      (node (ref "C66") (pin "2") (pinfunction "2_2") (pintype "passive"))
      (node (ref "C67") (pin "2") (pinfunction "2_2") (pintype "passive"))
      (node (ref "C68") (pin "2") (pinfunction "2_2") (pintype "passive"))
      (node (ref "C69") (pin "2") (pinfunction "2_2") (pintype "passive"))
      (node (ref "C70") (pin "2") (pinfunction "2_2") (pintype "passive"))
      (node (ref "C71") (pin "2") (pinfunction "2_2") (pintype "passive"))
      (node (ref "C72") (pin "2") (pinfunction "2_2") (pintype "passive"))
      (node (ref "C73") (pin "2") (pinfunction "2_2") (pintype "passive"))
      (node (ref "C74") (pin "2") (pinfunction "2_2") (pintype "passive"))
      (node (ref "C96") (pin "2") (pinfunction "2_2") (pintype "passive"))
      (node (ref "C97") (pin "2") (pinfunction "2_2") (pintype "passive"))
      (node (ref "C98") (pin "2") (pinfunction "2_2") (pintype "passive"))
      (node (ref "C99") (pin "2") (pinfunction "2_2") (pintype "passive"))
      (node (ref "J2") (pin "1") (pinfunction "1_1") (pintype "passive"))
      (node (ref "J2") (pin "2") (pinfunction "2_2") (pintype "passive"))
      (node (ref "J2") (pin "3") (pinfunction "3_3") (pintype "passive"))
      (node (ref "J2") (pin "4") (pinfunction "4_4") (pintype "passive"))
      (node (ref "J3") (pin "10") (pinfunction "10_10") (pintype "passive"))
      (node (ref "J3") (pin "11") (pinfunction "11_11") (pintype "passive"))
      (node (ref "J3") (pin "12") (pinfunction "12_12") (pintype "passive"))
      (node (ref "J3") (pin "3") (pinfunction "3_3") (pintype "passive"))
      (node (ref "J3") (pin "33") (pinfunction "33_33") (pintype "passive"))
      (node (ref "J3") (pin "34") (pinfunction "34_34") (pintype "passive"))
      (node (ref "J3") (pin "4") (pinfunction "4_4") (pintype "passive"))
      (node (ref "J3") (pin "9") (pinfunction "9_9") (pintype "passive"))
      (node (ref "J4") (pin "1") (pinfunction "1_1") (pintype "passive"))
      (node (ref "J4") (pin "2") (pinfunction "2_2") (pintype "passive"))
      (node (ref "J4") (pin "3") (pinfunction "3_3") (pintype "passive"))
      (node (ref "J4") (pin "4") (pinfunction "4_4") (pintype "passive"))
      (node (ref "J4") (pin "5") (pinfunction "5_5") (pintype "passive"))
      (node (ref "J4") (pin "6") (pinfunction "6_6") (pintype "passive"))
      (node (ref "J4") (pin "7") (pinfunction "7_7") (pintype "passive"))
      (node (ref "K1") (pin "2") (pintype "passive"))
      (node (ref "U3") (pin "A10") (pinfunction "MGTPRXN2_216_A10") (pintype "input"))
      (node (ref "U3") (pin "A11") (pinfunction "GND_A11") (pintype "power_in"))
      (node (ref "U3") (pin "A12") (pinfunction "GND_A12") (pintype "power_in"))
      (node (ref "U3") (pin "A2") (pinfunction "GND_A2") (pintype "power_in"))
      (node (ref "U3") (pin "A22") (pinfunction "GND_A22") (pintype "power_in"))
      (node (ref "U3") (pin "A3") (pinfunction "GND_A3") (pintype "power_in"))
      (node (ref "U3") (pin "A5") (pinfunction "GND_A5") (pintype "power_in"))
      (node (ref "U3") (pin "A7") (pinfunction "GND_A7") (pintype "power_in"))
      (node (ref "U3") (pin "A8") (pinfunction "MGTPRXN0_216_A8") (pintype "input"))
      (node (ref "U3") (pin "A9") (pinfunction "GND_A9") (pintype "power_in"))
      (node (ref "U3") (pin "AA12") (pinfunction "GND_AA12") (pintype "power_in"))
      (node (ref "U3") (pin "AA2") (pinfunction "GND_AA2") (pintype "power_in"))
      (node (ref "U3") (pin "AA22") (pinfunction "GND_AA22") (pintype "power_in"))
      (node (ref "U3") (pin "AB19") (pinfunction "GND_AB19") (pintype "power_in"))
      (node (ref "U3") (pin "AB9") (pinfunction "GND_AB9") (pintype "power_in"))
      (node (ref "U3") (pin "B10") (pinfunction "MGTPRXP2_216_B10") (pintype "input"))
      (node (ref "U3") (pin "B11") (pinfunction "MGTAVTT_B11") (pintype "power_in"))
      (node (ref "U3") (pin "B12") (pinfunction "GND_B12") (pintype "power_in"))
      (node (ref "U3") (pin "B19") (pinfunction "GND_B19") (pintype "power_in"))
      (node (ref "U3") (pin "B3") (pinfunction "GND_B3") (pintype "power_in"))
      (node (ref "U3") (pin "B5") (pinfunction "MGTAVTT_B5") (pintype "power_in"))
      (node (ref "U3") (pin "B7") (pinfunction "MGTAVTT_B7") (pintype "power_in"))
      (node (ref "U3") (pin "B8") (pinfunction "MGTPRXP0_216_B8") (pintype "input"))
      (node (ref "U3") (pin "B9") (pinfunction "MGTAVTT_B9") (pintype "power_in"))
      (node (ref "U3") (pin "C10") (pinfunction "GND_C10") (pintype "power_in"))
      (node (ref "U3") (pin "C11") (pinfunction "MGTPRXN1_216_C11") (pintype "input"))
      (node (ref "U3") (pin "C12") (pinfunction "GND_C12") (pintype "power_in"))
      (node (ref "U3") (pin "C16") (pinfunction "GND_C16") (pintype "power_in"))
      (node (ref "U3") (pin "C3") (pinfunction "GND_C3") (pintype "power_in"))
      (node (ref "U3") (pin "C4") (pinfunction "MGTAVTT_C4") (pintype "power_in"))
      (node (ref "U3") (pin "C6") (pinfunction "GND_C6") (pintype "power_in"))
      (node (ref "U3") (pin "C8") (pinfunction "MGTAVTT_C8") (pintype "power_in"))
      (node (ref "U3") (pin "C9") (pinfunction "MGTPRXN3_216_C9") (pintype "input"))
      (node (ref "U3") (pin "D10") (pinfunction "MGTAVCC_D10") (pintype "power_in"))
      (node (ref "U3") (pin "D11") (pinfunction "MGTPRXP1_216_D11") (pintype "input"))
      (node (ref "U3") (pin "D12") (pinfunction "GND_D12") (pintype "power_in"))
      (node (ref "U3") (pin "D13") (pinfunction "GND_D13") (pintype "power_in"))
      (node (ref "U3") (pin "D3") (pinfunction "GND_D3") (pintype "power_in"))
      (node (ref "U3") (pin "D4") (pinfunction "GND_D4") (pintype "power_in"))
      (node (ref "U3") (pin "D6") (pinfunction "MGTAVCC_D6") (pintype "power_in"))
      (node (ref "U3") (pin "D8") (pinfunction "GND_D8") (pintype "power_in"))
      (node (ref "U3") (pin "D9") (pinfunction "MGTPRXP3_216_D9") (pintype "input"))
      (node (ref "U3") (pin "E11") (pinfunction "GND_E11") (pintype "power_in"))
      (node (ref "U3") (pin "E12") (pinfunction "VCCBATT_0_E12") (pintype "power_in"))
      (node (ref "U3") (pin "E20") (pinfunction "GND_E20") (pintype "power_in"))
      (node (ref "U3") (pin "E4") (pinfunction "GND_E4") (pintype "power_in"))
      (node (ref "U3") (pin "E5") (pinfunction "GND_E5") (pintype "power_in"))
      (node (ref "U3") (pin "E7") (pinfunction "GND_E7") (pintype "power_in"))
      (node (ref "U3") (pin "E8") (pinfunction "MGTAVCC_E8") (pintype "power_in"))
      (node (ref "U3") (pin "E9") (pinfunction "GND_E9") (pintype "power_in"))
      (node (ref "U3") (pin "F11") (pinfunction "GND_F11") (pintype "power_in"))
      (node (ref "U3") (pin "F17") (pinfunction "GND_F17") (pintype "power_in"))
      (node (ref "U3") (pin "F5") (pinfunction "GND_F5") (pintype "power_in"))
      (node (ref "U3") (pin "F7") (pinfunction "MGTAVCC_F7") (pintype "power_in"))
      (node (ref "U3") (pin "F8") (pinfunction "MGTRREF_216_F8") (pintype "input"))
      (node (ref "U3") (pin "F9") (pinfunction "MGTAVCC_F9") (pintype "power_in"))
      (node (ref "U3") (pin "G10") (pinfunction "GND_G10") (pintype "power_in"))
      (node (ref "U3") (pin "G12") (pinfunction "GND_G12") (pintype "power_in"))
      (node (ref "U3") (pin "G14") (pinfunction "GND_G14") (pintype "power_in"))
      (node (ref "U3") (pin "G5") (pinfunction "GND_G5") (pintype "power_in"))
      (node (ref "U3") (pin "G6") (pinfunction "GND_G6") (pintype "power_in"))
      (node (ref "U3") (pin "G7") (pinfunction "GND_G7") (pintype "power_in"))
      (node (ref "U3") (pin "G8") (pinfunction "GND_G8") (pintype "power_in"))
      (node (ref "U3") (pin "G9") (pinfunction "GND_G9") (pintype "power_in"))
      (node (ref "U3") (pin "H1") (pinfunction "GND_H1") (pintype "power_in"))
      (node (ref "U3") (pin "H11") (pinfunction "GND_H11") (pintype "power_in"))
      (node (ref "U3") (pin "H21") (pinfunction "GND_H21") (pintype "power_in"))
      (node (ref "U3") (pin "H7") (pinfunction "GND_H7") (pintype "power_in"))
      (node (ref "U3") (pin "H9") (pinfunction "GND_H9") (pintype "power_in"))
      (node (ref "U3") (pin "J10") (pinfunction "GND_J10") (pintype "power_in"))
      (node (ref "U3") (pin "J12") (pinfunction "GND_J12") (pintype "power_in"))
      (node (ref "U3") (pin "J18") (pinfunction "GND_J18") (pintype "power_in"))
      (node (ref "U3") (pin "J8") (pinfunction "GND_J8") (pintype "power_in"))
      (node (ref "U3") (pin "K11") (pinfunction "GND_K11") (pintype "power_in"))
      (node (ref "U3") (pin "K15") (pinfunction "GND_K15") (pintype "power_in"))
      (node (ref "U3") (pin "K5") (pinfunction "GND_K5") (pintype "power_in"))
      (node (ref "U3") (pin "K7") (pinfunction "GND_K7") (pintype "power_in"))
      (node (ref "U3") (pin "K9") (pinfunction "GNDADC_0_K9") (pintype "power_in"))
      (node (ref "U3") (pin "L2") (pinfunction "GND_L2") (pintype "power_in"))
      (node (ref "U3") (pin "L22") (pinfunction "GND_L22") (pintype "power_in"))
      (node (ref "U3") (pin "L8") (pinfunction "GND_L8") (pintype "power_in"))
      (node (ref "U3") (pin "L9") (pinfunction "VREFN_0_L9") (pintype "input"))
      (node (ref "U3") (pin "M10") (pinfunction "VREFP_0_M10") (pintype "input"))
      (node (ref "U3") (pin "M11") (pinfunction "GND_M11") (pintype "power_in"))
      (node (ref "U3") (pin "M19") (pinfunction "GND_M19") (pintype "power_in"))
      (node (ref "U3") (pin "M7") (pinfunction "GND_M7") (pintype "power_in"))
      (node (ref "U3") (pin "N10") (pinfunction "DXP_0_N10") (pintype "input"))
      (node (ref "U3") (pin "N16") (pinfunction "GND_N16") (pintype "power_in"))
      (node (ref "U3") (pin "N6") (pinfunction "GND_N6") (pintype "power_in"))
      (node (ref "U3") (pin "N8") (pinfunction "GND_N8") (pintype "power_in"))
      (node (ref "U3") (pin "N9") (pinfunction "DXN_0_N9") (pintype "input"))
      (node (ref "U3") (pin "P11") (pinfunction "GND_P11") (pintype "power_in"))
      (node (ref "U3") (pin "P13") (pinfunction "GND_P13") (pintype "power_in"))
      (node (ref "U3") (pin "P3") (pinfunction "GND_P3") (pintype "power_in"))
      (node (ref "U3") (pin "P7") (pinfunction "GND_P7") (pintype "power_in"))
      (node (ref "U3") (pin "P9") (pinfunction "GND_P9") (pintype "power_in"))
      (node (ref "U3") (pin "R10") (pinfunction "GND_R10") (pintype "power_in"))
      (node (ref "U3") (pin "R12") (pinfunction "GND_R12") (pintype "power_in"))
      (node (ref "U3") (pin "R20") (pinfunction "GND_R20") (pintype "power_in"))
      (node (ref "U3") (pin "R8") (pinfunction "GND_R8") (pintype "power_in"))
      (node (ref "U3") (pin "T11") (pinfunction "GND_T11") (pintype "power_in"))
      (node (ref "U3") (pin "T17") (pinfunction "GND_T17") (pintype "power_in"))
      (node (ref "U3") (pin "T7") (pinfunction "GND_T7") (pintype "power_in"))
      (node (ref "U3") (pin "T9") (pinfunction "GND_T9") (pintype "power_in"))
      (node (ref "U3") (pin "U10") (pinfunction "M1_0_U10") (pintype "input"))
      (node (ref "U3") (pin "U14") (pinfunction "GND_U14") (pintype "power_in"))
      (node (ref "U3") (pin "U4") (pinfunction "GND_U4") (pintype "power_in"))
      (node (ref "U3") (pin "U9") (pinfunction "M2_0_U9") (pintype "input"))
      (node (ref "U3") (pin "V1") (pinfunction "GND_V1") (pintype "power_in"))
      (node (ref "U3") (pin "V11") (pinfunction "GND_V11") (pintype "power_in"))
      (node (ref "U3") (pin "V21") (pinfunction "GND_V21") (pintype "power_in"))
      (node (ref "U3") (pin "W18") (pinfunction "GND_W18") (pintype "power_in"))
      (node (ref "U3") (pin "W8") (pinfunction "GND_W8") (pintype "power_in"))
      (node (ref "U3") (pin "Y15") (pinfunction "GND_Y15") (pintype "power_in"))
      (node (ref "U3") (pin "Y5") (pinfunction "GND_Y5") (pintype "power_in"))
      (node (ref "U4") (pin "4") (pinfunction "VSS_4") (pintype "passive"))
      (node (ref "Y1") (pin "2") (pinfunction "2_2") (pintype "passive"))
    )
    (net (code "218") (name "Net-(R34-Pad1)") (class "Default")
      (node (ref "R34") (pin "1") (pintype "passive"))
      (node (ref "Y1") (pin "3") (pinfunction "3_3") (pintype "passive"))
    )
    (net (code "219") (name "Net-(R35-Pad1)") (class "Default")
      (node (ref "R35") (pin "1") (pintype "passive"))
      (node (ref "V1") (pin "1") (pinfunction "1_1") (pintype "passive"))
    )
    (net (code "220") (name "Net-(R63-Pad1)") (class "Default")
      (node (ref "R63") (pin "1") (pintype "passive"))
      (node (ref "V4") (pin "1") (pinfunction "1_1") (pintype "passive"))
    )
    (net (code "221") (name "Net-(R64-Pad1)") (class "Default")
      (node (ref "R64") (pin "1") (pintype "passive"))
      (node (ref "V3") (pin "1") (pinfunction "1_1") (pintype "passive"))
    )
    (net (code "222") (name "Net-(U3G-DONE_0)") (class "Default")
      (node (ref "R38") (pin "1") (pintype "passive"))
      (node (ref "U3") (pin "G11") (pinfunction "DONE_0_G11") (pintype "bidirectional"))
    )
    (net (code "223") (name "Net-(U3G-INIT_B_0)") (class "Default")
      (node (ref "R39") (pin "1") (pintype "passive"))
      (node (ref "U3") (pin "U12") (pinfunction "INIT_B_0_U12") (pintype "bidirectional"))
    )
    (net (code "224") (name "Net-(U3G-M0_0)") (class "Default")
      (node (ref "R37") (pin "1") (pintype "passive"))
      (node (ref "U3") (pin "U11") (pinfunction "M0_0_U11") (pintype "input"))
    )
    (net (code "225") (name "Net-(U3G-PROGRAM_B_0)") (class "Default")
      (node (ref "R40") (pin "1") (pintype "passive"))
      (node (ref "U3") (pin "N12") (pinfunction "PROGRAM_B_0_N12") (pintype "input"))
    )
    (net (code "226") (name "Net-(U4-CLK)") (class "Default")
      (node (ref "R33") (pin "1") (pintype "passive"))
      (node (ref "U4") (pin "6") (pinfunction "CLK_6") (pintype "passive"))
    )
    (net (code "227") (name "VDD1.0") (class "Default")
      (node (ref "C35") (pin "1") (pinfunction "1_1") (pintype "passive"))
      (node (ref "C36") (pin "1") (pinfunction "1_1") (pintype "passive"))
      (node (ref "C37") (pin "1") (pinfunction "1_1") (pintype "passive"))
      (node (ref "C38") (pin "1") (pinfunction "1_1") (pintype "passive"))
      (node (ref "C39") (pin "1") (pinfunction "1_1") (pintype "passive"))
      (node (ref "C40") (pin "1") (pinfunction "1_1") (pintype "passive"))
      (node (ref "C41") (pin "1") (pinfunction "1_1") (pintype "passive"))
      (node (ref "C42") (pin "1") (pinfunction "1_1") (pintype "passive"))
      (node (ref "C48") (pin "1") (pinfunction "1_1") (pintype "passive"))
      (node (ref "U3") (pin "H10") (pinfunction "VCCINT_H10") (pintype "power_in"))
      (node (ref "U3") (pin "H8") (pinfunction "VCCINT_H8") (pintype "power_in"))
      (node (ref "U3") (pin "J11") (pinfunction "VCCBRAM_J11") (pintype "power_in"))
      (node (ref "U3") (pin "J7") (pinfunction "VCCINT_J7") (pintype "power_in"))
      (node (ref "U3") (pin "J9") (pinfunction "VCCINT_J9") (pintype "power_in"))
      (node (ref "U3") (pin "K8") (pinfunction "VCCINT_K8") (pintype "power_in"))
      (node (ref "U3") (pin "L11") (pinfunction "VCCBRAM_L11") (pintype "power_in"))
      (node (ref "U3") (pin "L7") (pinfunction "VCCINT_L7") (pintype "power_in"))
      (node (ref "U3") (pin "M8") (pinfunction "VCCINT_M8") (pintype "power_in"))
      (node (ref "U3") (pin "N11") (pinfunction "VCCBRAM_N11") (pintype "power_in"))
      (node (ref "U3") (pin "N7") (pinfunction "VCCINT_N7") (pintype "power_in"))
      (node (ref "U3") (pin "P10") (pinfunction "VCCINT_P10") (pintype "power_in"))
      (node (ref "U3") (pin "P8") (pinfunction "VCCINT_P8") (pintype "power_in"))
      (node (ref "U3") (pin "R7") (pinfunction "VCCINT_R7") (pintype "power_in"))
      (node (ref "U3") (pin "R9") (pinfunction "VCCINT_R9") (pintype "power_in"))
      (node (ref "U3") (pin "T10") (pinfunction "VCCINT_T10") (pintype "power_in"))
      (node (ref "U3") (pin "T8") (pinfunction "VCCINT_T8") (pintype "power_in"))
    )
    (net (code "228") (name "VDD1.5") (class "Default")
      (node (ref "C100") (pin "1") (pinfunction "1_1") (pintype "passive"))
      (node (ref "C102") (pin "1") (pinfunction "1_1") (pintype "passive"))
      (node (ref "C103") (pin "1") (pinfunction "1_1") (pintype "passive"))
      (node (ref "C104") (pin "1") (pinfunction "1_1") (pintype "passive"))
      (node (ref "C99") (pin "1") (pinfunction "1_1") (pintype "passive"))
      (node (ref "U3") (pin "C1") (pinfunction "VCCO_35_C1") (pintype "power_in"))
      (node (ref "U3") (pin "F2") (pinfunction "VCCO_35_F2") (pintype "power_in"))
      (node (ref "U3") (pin "H6") (pinfunction "VCCO_35_H6") (pintype "power_in"))
      (node (ref "U3") (pin "J3") (pinfunction "VCCO_35_J3") (pintype "power_in"))
      (node (ref "U3") (pin "M4") (pinfunction "VCCO_35_M4") (pintype "power_in"))
      (node (ref "U3") (pin "N1") (pinfunction "VCCO_35_N1") (pintype "power_in"))
    )
    (net (code "229") (name "VDD1.8") (class "Default")
      (node (ref "C43") (pin "1") (pinfunction "1_1") (pintype "passive"))
      (node (ref "C44") (pin "1") (pinfunction "1_1") (pintype "passive"))
      (node (ref "C45") (pin "1") (pinfunction "1_1") (pintype "passive"))
      (node (ref "C46") (pin "1") (pinfunction "1_1") (pintype "passive"))
      (node (ref "C47") (pin "1") (pinfunction "1_1") (pintype "passive"))
      (node (ref "U3") (pin "H12") (pinfunction "VCCAUX_H12") (pintype "power_in"))
      (node (ref "U3") (pin "K10") (pinfunction "VCCADC_0_K10") (pintype "power_in"))
      (node (ref "U3") (pin "K12") (pinfunction "VCCAUX_K12") (pintype "power_in"))
      (node (ref "U3") (pin "M12") (pinfunction "VCCAUX_M12") (pintype "power_in"))
      (node (ref "U3") (pin "P12") (pinfunction "VCCAUX_P12") (pintype "power_in"))
      (node (ref "U3") (pin "R11") (pinfunction "VCCAUX_R11") (pintype "power_in"))
    )
    (net (code "230") (name "VDD3.3") (class "Default")
      (node (ref "C24") (pin "1") (pinfunction "1_1") (pintype "passive"))
      (node (ref "C33") (pin "1") (pinfunction "1_1") (pintype "passive"))
      (node (ref "C34") (pin "1") (pinfunction "1_1") (pintype "passive"))
      (node (ref "C55") (pin "1") (pinfunction "1_1") (pintype "passive"))
      (node (ref "C56") (pin "1") (pinfunction "1_1") (pintype "passive"))
      (node (ref "C57") (pin "1") (pinfunction "1_1") (pintype "passive"))
      (node (ref "C58") (pin "1") (pinfunction "1_1") (pintype "passive"))
      (node (ref "C59") (pin "1") (pinfunction "1_1") (pintype "passive"))
      (node (ref "C60") (pin "1") (pinfunction "1_1") (pintype "passive"))
      (node (ref "C61") (pin "1") (pinfunction "1_1") (pintype "passive"))
      (node (ref "C62") (pin "1") (pinfunction "1_1") (pintype "passive"))
      (node (ref "C63") (pin "1") (pinfunction "1_1") (pintype "passive"))
      (node (ref "C64") (pin "1") (pinfunction "1_1") (pintype "passive"))
      (node (ref "C65") (pin "1") (pinfunction "1_1") (pintype "passive"))
      (node (ref "C66") (pin "1") (pinfunction "1_1") (pintype "passive"))
      (node (ref "C67") (pin "1") (pinfunction "1_1") (pintype "passive"))
      (node (ref "C68") (pin "1") (pinfunction "1_1") (pintype "passive"))
      (node (ref "C69") (pin "1") (pinfunction "1_1") (pintype "passive"))
      (node (ref "C70") (pin "1") (pinfunction "1_1") (pintype "passive"))
      (node (ref "C71") (pin "1") (pinfunction "1_1") (pintype "passive"))
      (node (ref "C72") (pin "1") (pinfunction "1_1") (pintype "passive"))
      (node (ref "C73") (pin "1") (pinfunction "1_1") (pintype "passive"))
      (node (ref "C74") (pin "1") (pinfunction "1_1") (pintype "passive"))
      (node (ref "C96") (pin "1") (pinfunction "1_1") (pintype "passive"))
      (node (ref "C97") (pin "1") (pinfunction "1_1") (pintype "passive"))
      (node (ref "C98") (pin "1") (pinfunction "1_1") (pintype "passive"))
      (node (ref "J3") (pin "1") (pinfunction "1_1") (pintype "passive"))
      (node (ref "J3") (pin "2") (pinfunction "2_2") (pintype "passive"))
      (node (ref "J4") (pin "8") (pinfunction "8_8") (pintype "passive"))
      (node (ref "R30") (pin "2") (pintype "passive"))
      (node (ref "R31") (pin "2") (pintype "passive"))
      (node (ref "R32") (pin "1") (pintype "passive"))
      (node (ref "R35") (pin "2") (pintype "passive"))
      (node (ref "R36") (pin "2") (pintype "passive"))
      (node (ref "R37") (pin "2") (pintype "passive"))
      (node (ref "R38") (pin "2") (pintype "passive"))
      (node (ref "R39") (pin "2") (pintype "passive"))
      (node (ref "R40") (pin "2") (pintype "passive"))
      (node (ref "R63") (pin "2") (pintype "passive"))
      (node (ref "R64") (pin "2") (pintype "passive"))
      (node (ref "U3") (pin "AA17") (pinfunction "VCCO_13_AA17") (pintype "power_in"))
      (node (ref "U3") (pin "AA7") (pinfunction "VCCO_34_AA7") (pintype "power_in"))
      (node (ref "U3") (pin "AB14") (pinfunction "VCCO_13_AB14") (pintype "power_in"))
      (node (ref "U3") (pin "AB4") (pinfunction "VCCO_34_AB4") (pintype "power_in"))
      (node (ref "U3") (pin "F12") (pinfunction "VCCO_0_F12") (pintype "power_in"))
      (node (ref "U3") (pin "G19") (pinfunction "VCCO_15_G19") (pintype "power_in"))
      (node (ref "U3") (pin "H16") (pinfunction "VCCO_15_H16") (pintype "power_in"))
      (node (ref "U3") (pin "J13") (pinfunction "VCCO_15_J13") (pintype "power_in"))
      (node (ref "U3") (pin "K20") (pinfunction "VCCO_15_K20") (pintype "power_in"))
      (node (ref "U3") (pin "L17") (pinfunction "VCCO_15_L17") (pintype "power_in"))
      (node (ref "U3") (pin "M14") (pinfunction "VCCO_14_M14") (pintype "power_in"))
      (node (ref "U3") (pin "N21") (pinfunction "VCCO_15_N21") (pintype "power_in"))
      (node (ref "U3") (pin "P18") (pinfunction "VCCO_14_P18") (pintype "power_in"))
      (node (ref "U3") (pin "R15") (pinfunction "VCCO_14_R15") (pintype "power_in"))
      (node (ref "U3") (pin "R5") (pinfunction "VCCO_34_R5") (pintype "power_in"))
      (node (ref "U3") (pin "T12") (pinfunction "VCCO_0_T12") (pintype "power_in"))
      (node (ref "U3") (pin "T2") (pinfunction "VCCO_34_T2") (pintype "power_in"))
      (node (ref "U3") (pin "T22") (pinfunction "VCCO_14_T22") (pintype "power_in"))
      (node (ref "U3") (pin "U19") (pinfunction "VCCO_14_U19") (pintype "power_in"))
      (node (ref "U3") (pin "U8") (pinfunction "CFGBVS_0_U8") (pintype "input"))
      (node (ref "U3") (pin "V16") (pinfunction "VCCO_13_V16") (pintype "power_in"))
      (node (ref "U3") (pin "V6") (pinfunction "VCCO_34_V6") (pintype "power_in"))
      (node (ref "U3") (pin "W13") (pinfunction "VCCO_13_W13") (pintype "power_in"))
      (node (ref "U3") (pin "W3") (pinfunction "VCCO_34_W3") (pintype "power_in"))
      (node (ref "U3") (pin "Y10") (pinfunction "VCCO_13_Y10") (pintype "power_in"))
      (node (ref "U3") (pin "Y20") (pinfunction "VCCO_14_Y20") (pintype "power_in"))
      (node (ref "U4") (pin "8") (pinfunction "VCC_8") (pintype "passive"))
      (node (ref "Y1") (pin "4") (pinfunction "4_4") (pintype "passive"))
    )
    (net (code "231") (name "VDDIN") (class "Default")
      (node (ref "J3") (pin "5") (pinfunction "5_5") (pintype "passive"))
      (node (ref "J3") (pin "6") (pinfunction "6_6") (pintype "passive"))
      (node (ref "J3") (pin "7") (pinfunction "7_7") (pintype "passive"))
      (node (ref "J3") (pin "8") (pinfunction "8_8") (pintype "passive"))
    )
    (net (code "232") (name "VDDIO") (class "Default")
      (node (ref "C49") (pin "1") (pinfunction "1_1") (pintype "passive"))
      (node (ref "C50") (pin "1") (pinfunction "1_1") (pintype "passive"))
      (node (ref "C51") (pin "1") (pinfunction "1_1") (pintype "passive"))
      (node (ref "C52") (pin "1") (pinfunction "1_1") (pintype "passive"))
      (node (ref "C53") (pin "1") (pinfunction "1_1") (pintype "passive"))
      (node (ref "C54") (pin "1") (pinfunction "1_1") (pintype "passive"))
      (node (ref "U3") (pin "A17") (pinfunction "VCCO_16_A17") (pintype "power_in"))
      (node (ref "U3") (pin "B14") (pinfunction "VCCO_16_B14") (pintype "power_in"))
      (node (ref "U3") (pin "C21") (pinfunction "VCCO_16_C21") (pintype "power_in"))
      (node (ref "U3") (pin "D18") (pinfunction "VCCO_16_D18") (pintype "power_in"))
      (node (ref "U3") (pin "E15") (pinfunction "VCCO_16_E15") (pintype "power_in"))
      (node (ref "U3") (pin "F22") (pinfunction "VCCO_16_F22") (pintype "power_in"))
    )
    (net (code "233") (name "unconnected-(J3-Pad13)") (class "Default")
      (node (ref "J3") (pin "13") (pinfunction "13_13") (pintype "passive"))
    )
    (net (code "234") (name "unconnected-(J3-Pad14)") (class "Default")
      (node (ref "J3") (pin "14") (pinfunction "14_14") (pintype "passive"))
    )
    (net (code "235") (name "unconnected-(J3-Pad15)") (class "Default")
      (node (ref "J3") (pin "15") (pinfunction "15_15") (pintype "passive"))
    )
    (net (code "236") (name "unconnected-(J3-Pad16)") (class "Default")
      (node (ref "J3") (pin "16") (pinfunction "16_16") (pintype "passive"))
    )
    (net (code "237") (name "unconnected-(J3-Pad17)") (class "Default")
      (node (ref "J3") (pin "17") (pinfunction "17_17") (pintype "passive"))
    )
    (net (code "238") (name "unconnected-(J3-Pad18)") (class "Default")
      (node (ref "J3") (pin "18") (pinfunction "18_18") (pintype "passive"))
    )
    (net (code "239") (name "unconnected-(J3-Pad19)") (class "Default")
      (node (ref "J3") (pin "19") (pinfunction "19_19") (pintype "passive"))
    )
    (net (code "240") (name "unconnected-(J3-Pad20)") (class "Default")
      (node (ref "J3") (pin "20") (pinfunction "20_20") (pintype "passive"))
    )
    (net (code "241") (name "unconnected-(J3-Pad21)") (class "Default")
      (node (ref "J3") (pin "21") (pinfunction "21_21") (pintype "passive"))
    )
    (net (code "242") (name "unconnected-(J3-Pad22)") (class "Default")
      (node (ref "J3") (pin "22") (pinfunction "22_22") (pintype "passive"))
    )
    (net (code "243") (name "unconnected-(J3-Pad23)") (class "Default")
      (node (ref "J3") (pin "23") (pinfunction "23_23") (pintype "passive"))
    )
    (net (code "244") (name "unconnected-(J3-Pad24)") (class "Default")
      (node (ref "J3") (pin "24") (pinfunction "24_24") (pintype "passive"))
    )
    (net (code "245") (name "unconnected-(J3-Pad25)") (class "Default")
      (node (ref "J3") (pin "25") (pinfunction "25_25") (pintype "passive"))
    )
    (net (code "246") (name "unconnected-(J3-Pad26)") (class "Default")
      (node (ref "J3") (pin "26") (pinfunction "26_26") (pintype "passive"))
    )
    (net (code "247") (name "unconnected-(J3-Pad28)") (class "Default")
      (node (ref "J3") (pin "28") (pinfunction "28_28") (pintype "passive"))
    )
    (net (code "248") (name "unconnected-(J3-Pad30)") (class "Default")
      (node (ref "J3") (pin "30") (pinfunction "30_30") (pintype "passive"))
    )
    (net (code "249") (name "unconnected-(J3-Pad32)") (class "Default")
      (node (ref "J3") (pin "32") (pinfunction "32_32") (pintype "passive"))
    )
    (net (code "250") (name "unconnected-(J4-Pad13)") (class "Default")
      (node (ref "J4") (pin "13") (pinfunction "13_13") (pintype "passive"))
    )
    (net (code "251") (name "unconnected-(J4-Pad14)") (class "Default")
      (node (ref "J4") (pin "14") (pinfunction "14_14") (pintype "passive"))
    )
    (net (code "252") (name "unconnected-(U3H-MGTPTXN0_216-PadA4)") (class "Default")
      (node (ref "U3") (pin "A4") (pinfunction "MGTPTXN0_216_A4") (pintype "output"))
    )
    (net (code "253") (name "unconnected-(U3H-MGTPTXN1_216-PadC5)") (class "Default")
      (node (ref "U3") (pin "C5") (pinfunction "MGTPTXN1_216_C5") (pintype "output"))
    )
    (net (code "254") (name "unconnected-(U3H-MGTPTXN2_216-PadA6)") (class "Default")
      (node (ref "U3") (pin "A6") (pinfunction "MGTPTXN2_216_A6") (pintype "output"))
    )
    (net (code "255") (name "unconnected-(U3H-MGTPTXN3_216-PadC7)") (class "Default")
      (node (ref "U3") (pin "C7") (pinfunction "MGTPTXN3_216_C7") (pintype "output"))
    )
    (net (code "256") (name "unconnected-(U3H-MGTPTXP0_216-PadB4)") (class "Default")
      (node (ref "U3") (pin "B4") (pinfunction "MGTPTXP0_216_B4") (pintype "output"))
    )
    (net (code "257") (name "unconnected-(U3H-MGTPTXP1_216-PadD5)") (class "Default")
      (node (ref "U3") (pin "D5") (pinfunction "MGTPTXP1_216_D5") (pintype "output"))
    )
    (net (code "258") (name "unconnected-(U3H-MGTPTXP2_216-PadB6)") (class "Default")
      (node (ref "U3") (pin "B6") (pinfunction "MGTPTXP2_216_B6") (pintype "output"))
    )
    (net (code "259") (name "unconnected-(U3H-MGTPTXP3_216-PadD7)") (class "Default")
      (node (ref "U3") (pin "D7") (pinfunction "MGTPTXP3_216_D7") (pintype "output"))
    )
    (net (code "260") (name "unconnected-(U3H-MGTREFCLK0N_216-PadE6)") (class "Default")
      (node (ref "U3") (pin "E6") (pinfunction "MGTREFCLK0N_216_E6") (pintype "input"))
    )
    (net (code "261") (name "unconnected-(U3H-MGTREFCLK0P_216-PadF6)") (class "Default")
      (node (ref "U3") (pin "F6") (pinfunction "MGTREFCLK0P_216_F6") (pintype "input"))
    )
    (net (code "262") (name "unconnected-(U3H-MGTREFCLK1N_216-PadE10)") (class "Default")
      (node (ref "U3") (pin "E10") (pinfunction "MGTREFCLK1N_216_E10") (pintype "input"))
    )
    (net (code "263") (name "unconnected-(U3H-MGTREFCLK1P_216-PadF10)") (class "Default")
      (node (ref "U3") (pin "F10") (pinfunction "MGTREFCLK1P_216_F10") (pintype "input"))
    )
    (net (code "264") (name "unconnected-(Y1-Pad1)") (class "Default")
      (node (ref "Y1") (pin "1") (pinfunction "1_1") (pintype "passive+no_connect"))
    )
  )
)
